# MUX1.net
KiCad netlist of a schematic drawn in EAGLE
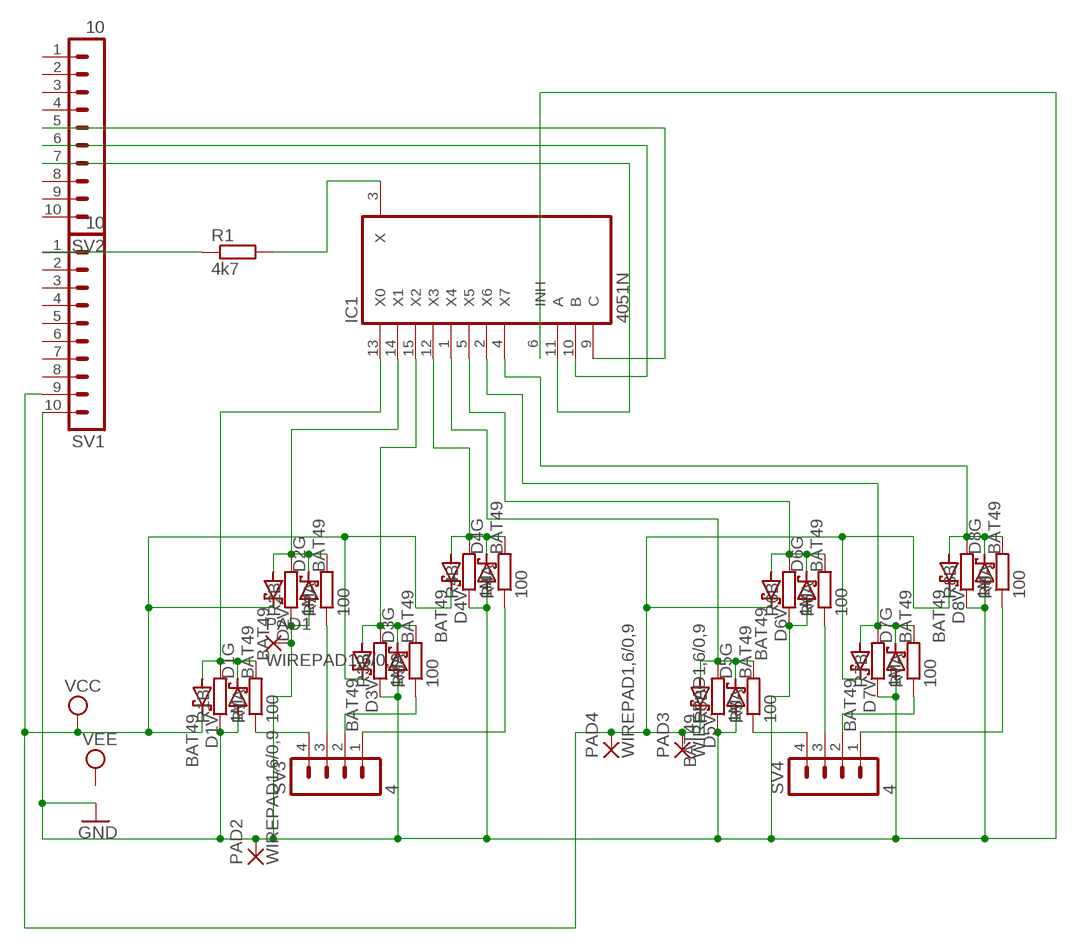
[diagram p0: schematic, sheet 1]

(export (version "E")
  (design (tool "Eeschema 10.0.6"))
  (components
    (comp (ref "D1G")
      (value "BAT49")
      (footprint "eagle-import:DO41-10")
      (libsource (lib "eagle-import") (part "BAT49"))
    )
    (comp (ref "D1V")
      (value "BAT49")
      (footprint "eagle-import:DO41-10")
      (libsource (lib "eagle-import") (part "BAT49"))
    )
    (comp (ref "D2G")
      (value "BAT49")
      (footprint "eagle-import:DO41-10")
      (libsource (lib "eagle-import") (part "BAT49"))
    )
    (comp (ref "D2V")
      (value "BAT49")
      (footprint "eagle-import:DO41-10")
      (libsource (lib "eagle-import") (part "BAT49"))
    )
    (comp (ref "D3G")
      (value "BAT49")
      (footprint "eagle-import:DO41-10")
      (libsource (lib "eagle-import") (part "BAT49"))
    )
    (comp (ref "D3V")
      (value "BAT49")
      (footprint "eagle-import:DO41-10")
      (libsource (lib "eagle-import") (part "BAT49"))
    )
    (comp (ref "D4G")
      (value "BAT49")
      (footprint "eagle-import:DO41-10")
      (libsource (lib "eagle-import") (part "BAT49"))
    )
    (comp (ref "D4V")
      (value "BAT49")
      (footprint "eagle-import:DO41-10")
      (libsource (lib "eagle-import") (part "BAT49"))
    )
    (comp (ref "D5G")
      (value "BAT49")
      (footprint "eagle-import:DO41-10")
      (libsource (lib "eagle-import") (part "BAT49"))
    )
    (comp (ref "D5V")
      (value "BAT49")
      (footprint "eagle-import:DO41-10")
      (libsource (lib "eagle-import") (part "BAT49"))
    )
    (comp (ref "D6G")
      (value "BAT49")
      (footprint "eagle-import:DO41-10")
      (libsource (lib "eagle-import") (part "BAT49"))
    )
    (comp (ref "D6V")
      (value "BAT49")
      (footprint "eagle-import:DO41-10")
      (libsource (lib "eagle-import") (part "BAT49"))
    )
    (comp (ref "D7G")
      (value "BAT49")
      (footprint "eagle-import:DO41-10")
      (libsource (lib "eagle-import") (part "BAT49"))
    )
    (comp (ref "D7V")
      (value "BAT49")
      (footprint "eagle-import:DO41-10")
      (libsource (lib "eagle-import") (part "BAT49"))
    )
    (comp (ref "D8G")
      (value "BAT49")
      (footprint "eagle-import:DO41-10")
      (libsource (lib "eagle-import") (part "BAT49"))
    )
    (comp (ref "D8V")
      (value "BAT49")
      (footprint "eagle-import:DO41-10")
      (libsource (lib "eagle-import") (part "BAT49"))
    )
    (comp (ref "IC1")
      (value "4051N")
      (footprint "eagle-import:DIL16")
      (libsource (lib "eagle-import") (part "4051N"))
    )
    (comp (ref "PAD1")
      (value "WIREPAD1,6/0,9")
      (footprint "eagle-import:1,6_0,9")
      (libsource (lib "eagle-import") (part "WIREPAD1,6/0,9"))
    )
    (comp (ref "PAD2")
      (value "WIREPAD1,6/0,9")
      (footprint "eagle-import:1,6_0,9")
      (libsource (lib "eagle-import") (part "WIREPAD1,6/0,9"))
    )
    (comp (ref "PAD3")
      (value "WIREPAD1,6/0,9")
      (footprint "eagle-import:1,6_0,9")
      (libsource (lib "eagle-import") (part "WIREPAD1,6/0,9"))
    )
    (comp (ref "PAD4")
      (value "WIREPAD1,6/0,9")
      (footprint "eagle-import:1,6_0,9")
      (libsource (lib "eagle-import") (part "WIREPAD1,6/0,9"))
    )
    (comp (ref "R1")
      (value "4k7")
      (footprint "eagle-import:0204_7")
      (libsource (lib "eagle-import") (part "R-EU_0204/7"))
    )
    (comp (ref "R1A")
      (value "100")
      (footprint "eagle-import:0204_7")
      (libsource (lib "eagle-import") (part "R-EU_0204/7"))
    )
    (comp (ref "R1B")
      (value "1M")
      (footprint "eagle-import:0204_7")
      (libsource (lib "eagle-import") (part "R-EU_0204/7"))
    )
    (comp (ref "R2A")
      (value "100")
      (footprint "eagle-import:0204_7")
      (libsource (lib "eagle-import") (part "R-EU_0204/7"))
    )
    (comp (ref "R2B")
      (value "1M")
      (footprint "eagle-import:0204_7")
      (libsource (lib "eagle-import") (part "R-EU_0204/7"))
    )
    (comp (ref "R3A")
      (value "100")
      (footprint "eagle-import:0204_7")
      (libsource (lib "eagle-import") (part "R-EU_0204/7"))
    )
    (comp (ref "R3B")
      (value "1M")
      (footprint "eagle-import:0204_7")
      (libsource (lib "eagle-import") (part "R-EU_0204/7"))
    )
    (comp (ref "R4A")
      (value "100")
      (footprint "eagle-import:0204_7")
      (libsource (lib "eagle-import") (part "R-EU_0204/7"))
    )
    (comp (ref "R4B")
      (value "1M")
      (footprint "eagle-import:0204_7")
      (libsource (lib "eagle-import") (part "R-EU_0204/7"))
    )
    (comp (ref "R5A")
      (value "100")
      (footprint "eagle-import:0204_7")
      (libsource (lib "eagle-import") (part "R-EU_0204/7"))
    )
    (comp (ref "R5B")
      (value "1M")
      (footprint "eagle-import:0204_7")
      (libsource (lib "eagle-import") (part "R-EU_0204/7"))
    )
    (comp (ref "R6A")
      (value "100")
      (footprint "eagle-import:0204_7")
      (libsource (lib "eagle-import") (part "R-EU_0204/7"))
    )
    (comp (ref "R6B")
      (value "1M")
      (footprint "eagle-import:0204_7")
      (libsource (lib "eagle-import") (part "R-EU_0204/7"))
    )
    (comp (ref "R7A")
      (value "100")
      (footprint "eagle-import:0204_7")
      (libsource (lib "eagle-import") (part "R-EU_0204/7"))
    )
    (comp (ref "R7B")
      (value "1M")
      (footprint "eagle-import:0204_7")
      (libsource (lib "eagle-import") (part "R-EU_0204/7"))
    )
    (comp (ref "R8A")
      (value "100")
      (footprint "eagle-import:0204_7")
      (libsource (lib "eagle-import") (part "R-EU_0204/7"))
    )
    (comp (ref "R8B")
      (value "1M")
      (footprint "eagle-import:0204_7")
      (libsource (lib "eagle-import") (part "R-EU_0204/7"))
    )
    (comp (ref "SV1")
      (value "10")
      (footprint "eagle-import:MA10-1")
      (libsource (lib "eagle-import") (part "MA10-1"))
    )
    (comp (ref "SV2")
      (value "10")
      (footprint "eagle-import:MA10-1")
      (libsource (lib "eagle-import") (part "MA10-1"))
    )
    (comp (ref "SV3")
      (value "4")
      (footprint "eagle-import:MA04-1")
      (libsource (lib "eagle-import") (part "MA04-1"))
    )
    (comp (ref "SV4")
      (value "4")
      (footprint "eagle-import:MA04-1")
      (libsource (lib "eagle-import") (part "MA04-1"))
    )
  )
  (nets
    (net (code "1") (name "GND") (class "Default")
      (node (ref "D1G") (pin "A") (pinfunction "A_A") (pintype "passive"))
      (node (ref "D2G") (pin "A") (pinfunction "A_A") (pintype "passive"))
      (node (ref "D3G") (pin "A") (pinfunction "A_A") (pintype "passive"))
      (node (ref "D4G") (pin "A") (pinfunction "A_A") (pintype "passive"))
      (node (ref "D5G") (pin "A") (pinfunction "A_A") (pintype "passive"))
      (node (ref "D6G") (pin "A") (pinfunction "A_A") (pintype "passive"))
      (node (ref "D7G") (pin "A") (pinfunction "A_A") (pintype "passive"))
      (node (ref "D8G") (pin "A") (pinfunction "A_A") (pintype "passive"))
      (node (ref "IC1") (pin "6") (pinfunction "INH_6") (pintype "input"))
      (node (ref "PAD1") (pin "1") (pinfunction "P_1") (pintype "passive"))
      (node (ref "PAD2") (pin "1") (pinfunction "P_1") (pintype "passive"))
      (node (ref "R1B") (pin "1") (pinfunction "1_1") (pintype "passive"))
      (node (ref "R2B") (pin "1") (pinfunction "1_1") (pintype "passive"))
      (node (ref "R3B") (pin "1") (pinfunction "1_1") (pintype "passive"))
      (node (ref "R4B") (pin "1") (pinfunction "1_1") (pintype "passive"))
      (node (ref "R5B") (pin "1") (pinfunction "1_1") (pintype "passive"))
      (node (ref "R6B") (pin "1") (pinfunction "1_1") (pintype "passive"))
      (node (ref "R7B") (pin "1") (pinfunction "1_1") (pintype "passive"))
      (node (ref "R8B") (pin "1") (pinfunction "1_1") (pintype "passive"))
      (node (ref "SV1") (pin "10") (pinfunction "10_10") (pintype "passive"))
    )
    (net (code "2") (name "Net-(IC1A-A)") (class "Default")
      (node (ref "IC1") (pin "11") (pinfunction "A_11") (pintype "input"))
      (node (ref "SV2") (pin "7") (pinfunction "7_7") (pintype "passive"))
    )
    (net (code "3") (name "Net-(IC1A-B)") (class "Default")
      (node (ref "IC1") (pin "10") (pinfunction "B_10") (pintype "input"))
      (node (ref "SV2") (pin "6") (pinfunction "6_6") (pintype "passive"))
    )
    (net (code "4") (name "Net-(IC1A-C)") (class "Default")
      (node (ref "IC1") (pin "9") (pinfunction "C_9") (pintype "input"))
      (node (ref "SV2") (pin "5") (pinfunction "5_5") (pintype "passive"))
    )
    (net (code "5") (name "Net-(IC1A-X)") (class "Default")
      (node (ref "IC1") (pin "3") (pinfunction "X_3") (pintype "bidirectional"))
      (node (ref "R1") (pin "2") (pinfunction "2_2") (pintype "passive"))
    )
    (net (code "6") (name "Net-(IC1A-X0)") (class "Default")
      (node (ref "D1G") (pin "C") (pinfunction "C_C") (pintype "passive"))
      (node (ref "D1V") (pin "A") (pinfunction "A_A") (pintype "passive"))
      (node (ref "IC1") (pin "13") (pinfunction "X0_13") (pintype "bidirectional"))
      (node (ref "R1A") (pin "2") (pinfunction "2_2") (pintype "passive"))
      (node (ref "R1B") (pin "2") (pinfunction "2_2") (pintype "passive"))
    )
    (net (code "7") (name "Net-(IC1A-X1)") (class "Default")
      (node (ref "D2G") (pin "C") (pinfunction "C_C") (pintype "passive"))
      (node (ref "D2V") (pin "A") (pinfunction "A_A") (pintype "passive"))
      (node (ref "IC1") (pin "14") (pinfunction "X1_14") (pintype "bidirectional"))
      (node (ref "R2A") (pin "2") (pinfunction "2_2") (pintype "passive"))
      (node (ref "R2B") (pin "2") (pinfunction "2_2") (pintype "passive"))
    )
    (net (code "8") (name "Net-(IC1A-X2)") (class "Default")
      (node (ref "D3G") (pin "C") (pinfunction "C_C") (pintype "passive"))
      (node (ref "D3V") (pin "A") (pinfunction "A_A") (pintype "passive"))
      (node (ref "IC1") (pin "15") (pinfunction "X2_15") (pintype "bidirectional"))
      (node (ref "R3A") (pin "2") (pinfunction "2_2") (pintype "passive"))
      (node (ref "R3B") (pin "2") (pinfunction "2_2") (pintype "passive"))
    )
    (net (code "9") (name "Net-(IC1A-X3)") (class "Default")
      (node (ref "D4G") (pin "C") (pinfunction "C_C") (pintype "passive"))
      (node (ref "D4V") (pin "A") (pinfunction "A_A") (pintype "passive"))
      (node (ref "IC1") (pin "12") (pinfunction "X3_12") (pintype "bidirectional"))
      (node (ref "R4A") (pin "2") (pinfunction "2_2") (pintype "passive"))
      (node (ref "R4B") (pin "2") (pinfunction "2_2") (pintype "passive"))
    )
    (net (code "10") (name "Net-(IC1A-X4)") (class "Default")
      (node (ref "D5G") (pin "C") (pinfunction "C_C") (pintype "passive"))
      (node (ref "D5V") (pin "A") (pinfunction "A_A") (pintype "passive"))
      (node (ref "IC1") (pin "1") (pinfunction "X4_1") (pintype "bidirectional"))
      (node (ref "R5A") (pin "2") (pinfunction "2_2") (pintype "passive"))
      (node (ref "R5B") (pin "2") (pinfunction "2_2") (pintype "passive"))
    )
    (net (code "11") (name "Net-(IC1A-X5)") (class "Default")
      (node (ref "D6G") (pin "C") (pinfunction "C_C") (pintype "passive"))
      (node (ref "D6V") (pin "A") (pinfunction "A_A") (pintype "passive"))
      (node (ref "IC1") (pin "5") (pinfunction "X5_5") (pintype "bidirectional"))
      (node (ref "R6A") (pin "2") (pinfunction "2_2") (pintype "passive"))
      (node (ref "R6B") (pin "2") (pinfunction "2_2") (pintype "passive"))
    )
    (net (code "12") (name "Net-(IC1A-X6)") (class "Default")
      (node (ref "D7G") (pin "C") (pinfunction "C_C") (pintype "passive"))
      (node (ref "D7V") (pin "A") (pinfunction "A_A") (pintype "passive"))
      (node (ref "IC1") (pin "2") (pinfunction "X6_2") (pintype "bidirectional"))
      (node (ref "R7A") (pin "2") (pinfunction "2_2") (pintype "passive"))
      (node (ref "R7B") (pin "2") (pinfunction "2_2") (pintype "passive"))
    )
    (net (code "13") (name "Net-(IC1A-X7)") (class "Default")
      (node (ref "D8G") (pin "C") (pinfunction "C_C") (pintype "passive"))
      (node (ref "D8V") (pin "A") (pinfunction "A_A") (pintype "passive"))
      (node (ref "IC1") (pin "4") (pinfunction "X7_4") (pintype "bidirectional"))
      (node (ref "R8A") (pin "2") (pinfunction "2_2") (pintype "passive"))
      (node (ref "R8B") (pin "2") (pinfunction "2_2") (pintype "passive"))
    )
    (net (code "14") (name "Net-(R1-Pad1)") (class "Default")
      (node (ref "R1") (pin "1") (pinfunction "1_1") (pintype "passive"))
      (node (ref "SV1") (pin "1") (pinfunction "1_1") (pintype "passive"))
    )
    (net (code "15") (name "Net-(R1A-Pad1)") (class "Default")
      (node (ref "R1A") (pin "1") (pinfunction "1_1") (pintype "passive"))
      (node (ref "SV3") (pin "4") (pinfunction "4_4") (pintype "passive"))
    )
    (net (code "16") (name "Net-(R2A-Pad1)") (class "Default")
      (node (ref "R2A") (pin "1") (pinfunction "1_1") (pintype "passive"))
      (node (ref "SV3") (pin "3") (pinfunction "3_3") (pintype "passive"))
    )
    (net (code "17") (name "Net-(R3A-Pad1)") (class "Default")
      (node (ref "R3A") (pin "1") (pinfunction "1_1") (pintype "passive"))
      (node (ref "SV3") (pin "2") (pinfunction "2_2") (pintype "passive"))
    )
    (net (code "18") (name "Net-(R4A-Pad1)") (class "Default")
      (node (ref "R4A") (pin "1") (pinfunction "1_1") (pintype "passive"))
      (node (ref "SV3") (pin "1") (pinfunction "1_1") (pintype "passive"))
    )
    (net (code "19") (name "Net-(R5A-Pad1)") (class "Default")
      (node (ref "R5A") (pin "1") (pinfunction "1_1") (pintype "passive"))
      (node (ref "SV4") (pin "4") (pinfunction "4_4") (pintype "passive"))
    )
    (net (code "20") (name "Net-(R6A-Pad1)") (class "Default")
      (node (ref "R6A") (pin "1") (pinfunction "1_1") (pintype "passive"))
      (node (ref "SV4") (pin "3") (pinfunction "3_3") (pintype "passive"))
    )
    (net (code "21") (name "Net-(R7A-Pad1)") (class "Default")
      (node (ref "R7A") (pin "1") (pinfunction "1_1") (pintype "passive"))
      (node (ref "SV4") (pin "2") (pinfunction "2_2") (pintype "passive"))
    )
    (net (code "22") (name "Net-(R8A-Pad1)") (class "Default")
      (node (ref "R8A") (pin "1") (pinfunction "1_1") (pintype "passive"))
      (node (ref "SV4") (pin "1") (pinfunction "1_1") (pintype "passive"))
    )
    (net (code "23") (name "VCC") (class "Default")
      (node (ref "D1V") (pin "C") (pinfunction "C_C") (pintype "passive"))
      (node (ref "D2V") (pin "C") (pinfunction "C_C") (pintype "passive"))
      (node (ref "D3V") (pin "C") (pinfunction "C_C") (pintype "passive"))
      (node (ref "D4V") (pin "C") (pinfunction "C_C") (pintype "passive"))
      (node (ref "D5V") (pin "C") (pinfunction "C_C") (pintype "passive"))
      (node (ref "D6V") (pin "C") (pinfunction "C_C") (pintype "passive"))
      (node (ref "D7V") (pin "C") (pinfunction "C_C") (pintype "passive"))
      (node (ref "D8V") (pin "C") (pinfunction "C_C") (pintype "passive"))
      (node (ref "PAD3") (pin "1") (pinfunction "P_1") (pintype "passive"))
      (node (ref "PAD4") (pin "1") (pinfunction "P_1") (pintype "passive"))
      (node (ref "SV1") (pin "9") (pinfunction "9_9") (pintype "passive"))
    )
    (net (code "25") (name "unconnected-(SV1-Pad2)") (class "Default")
      (node (ref "SV1") (pin "2") (pinfunction "2_2") (pintype "passive"))
    )
    (net (code "26") (name "unconnected-(SV1-Pad3)") (class "Default")
      (node (ref "SV1") (pin "3") (pinfunction "3_3") (pintype "passive"))
    )
    (net (code "27") (name "unconnected-(SV1-Pad4)") (class "Default")
      (node (ref "SV1") (pin "4") (pinfunction "4_4") (pintype "passive"))
    )
    (net (code "28") (name "unconnected-(SV1-Pad5)") (class "Default")
      (node (ref "SV1") (pin "5") (pinfunction "5_5") (pintype "passive"))
    )
    (net (code "29") (name "unconnected-(SV1-Pad6)") (class "Default")
      (node (ref "SV1") (pin "6") (pinfunction "6_6") (pintype "passive"))
    )
    (net (code "30") (name "unconnected-(SV1-Pad7)") (class "Default")
      (node (ref "SV1") (pin "7") (pinfunction "7_7") (pintype "passive"))
    )
    (net (code "31") (name "unconnected-(SV1-Pad8)") (class "Default")
      (node (ref "SV1") (pin "8") (pinfunction "8_8") (pintype "passive"))
    )
    (net (code "32") (name "unconnected-(SV2-Pad1)") (class "Default")
      (node (ref "SV2") (pin "1") (pinfunction "1_1") (pintype "passive"))
    )
    (net (code "33") (name "unconnected-(SV2-Pad2)") (class "Default")
      (node (ref "SV2") (pin "2") (pinfunction "2_2") (pintype "passive"))
    )
    (net (code "34") (name "unconnected-(SV2-Pad3)") (class "Default")
      (node (ref "SV2") (pin "3") (pinfunction "3_3") (pintype "passive"))
    )
    (net (code "35") (name "unconnected-(SV2-Pad4)") (class "Default")
      (node (ref "SV2") (pin "4") (pinfunction "4_4") (pintype "passive"))
    )
    (net (code "36") (name "unconnected-(SV2-Pad8)") (class "Default")
      (node (ref "SV2") (pin "8") (pinfunction "8_8") (pintype "passive"))
    )
    (net (code "37") (name "unconnected-(SV2-Pad9)") (class "Default")
      (node (ref "SV2") (pin "9") (pinfunction "9_9") (pintype "passive"))
    )
    (net (code "38") (name "unconnected-(SV2-Pad10)") (class "Default")
      (node (ref "SV2") (pin "10") (pinfunction "10_10") (pintype "passive"))
    )
  )
)
